# Schematic.net
KiCad netlist of a schematic drawn in Altium Designer
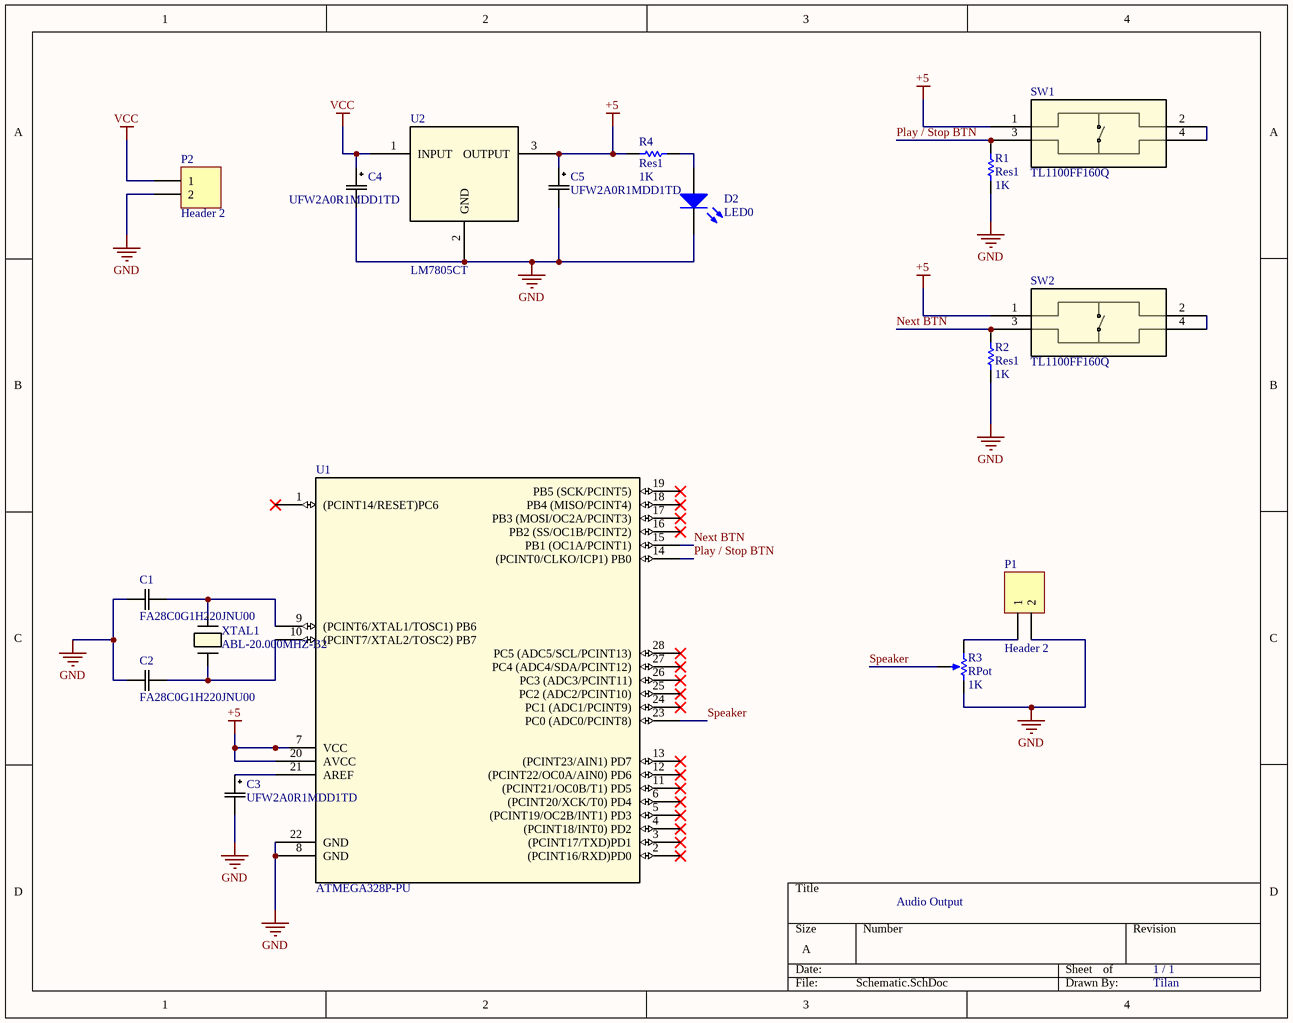
[diagram p0: Schematic.SchDoc]

(export (version "E")
  (design (tool "Eeschema 10.0.6"))
  (components
    (comp (ref "C1")
      (value "FA28C0G1H220JNU00")
      (footprint "CAP_FA28_TDK")
      (description "No Description Available")
      (fields (field (name "COPYRIGHT") "Copyright (C) 2018 Accelerated Designs. All rights reserved"))
      (libsource (lib "22pfcap") (part "FA28C0G1H220JNU00"))
    )
    (comp (ref "C2")
      (value "FA28C0G1H220JNU00")
      (footprint "CAP_FA28_TDK")
      (description "No Description Available")
      (fields (field (name "COPYRIGHT") "Copyright (C) 2018 Accelerated Designs. All rights reserved"))
      (libsource (lib "22pfcap") (part "FA28C0G1H220JNU00"))
    )
    (comp (ref "C3")
      (value "UFW2A0R1MDD1TD")
      (footprint "CAP_UEP_5X11_NCH")
      (description "No Description Available")
      (fields (field (name "COPYRIGHT") "Copyright (C) 2018 Accelerated Designs. All rights reserved"))
      (libsource (lib "Pollcap") (part "UFW2A0R1MDD1TD"))
    )
    (comp (ref "C4")
      (value "UFW2A0R1MDD1TD")
      (footprint "CAP_UEP_5X11_NCH")
      (description "No Description Available")
      (fields (field (name "COPYRIGHT") "Copyright (C) 2018 Accelerated Designs. All rights reserved"))
      (libsource (lib "Pollcap") (part "UFW2A0R1MDD1TD"))
    )
    (comp (ref "C5")
      (value "UFW2A0R1MDD1TD")
      (footprint "CAP_UEP_5X11_NCH")
      (description "No Description Available")
      (fields (field (name "COPYRIGHT") "Copyright (C) 2018 Accelerated Designs. All rights reserved"))
      (libsource (lib "Pollcap") (part "UFW2A0R1MDD1TD"))
    )
    (comp (ref "D2")
      (value "LED0")
      (footprint "LED-0")
      (description "Typical INFRARED GaAs LED")
      (fields (field (name "PUBLISHER") "Altium Limited"))
      (libsource (lib "Miscellaneous Devices") (part "LED0"))
    )
    (comp (ref "P1")
      (value "Header 2")
      (footprint "HDR1X2")
      (description "Header, 2-Pin")
      (fields (field (name "PUBLISHER") "Altium Limited"))
      (libsource (lib "Miscellaneous Connectors") (part "Header 2"))
    )
    (comp (ref "P2")
      (value "Header 2")
      (footprint "HDR1X2")
      (description "Header, 2-Pin")
      (fields (field (name "PUBLISHER") "Altium Limited"))
      (libsource (lib "") (part "Header 2_1"))
    )
    (comp (ref "R1")
      (value "Res1")
      (footprint "AXIAL-0.3")
      (description "Resistor")
      (fields (field (name "ALTIUM_VALUE") "1K") (field (name "PUBLISHER") "Altium Limited"))
      (libsource (lib "Miscellaneous Devices") (part "Res1"))
    )
    (comp (ref "R2")
      (value "Res1")
      (footprint "AXIAL-0.3")
      (description "Resistor")
      (fields (field (name "ALTIUM_VALUE") "1K") (field (name "PUBLISHER") "Altium Limited"))
      (libsource (lib "Miscellaneous Devices") (part "Res1"))
    )
    (comp (ref "R3")
      (value "RPot")
      (footprint "VR5")
      (description "Potentiometer")
      (fields (field (name "ALTIUM_VALUE") "1K") (field (name "PUBLISHER") "Altium Limited"))
      (libsource (lib "Miscellaneous Devices") (part "RPot"))
    )
    (comp (ref "R4")
      (value "Res1")
      (footprint "AXIAL-0.3")
      (description "Resistor")
      (fields (field (name "ALTIUM_VALUE") "1K") (field (name "PUBLISHER") "Altium Limited"))
      (libsource (lib "Miscellaneous Devices") (part "Res1"))
    )
    (comp (ref "SW1")
      (value "TL1100FF160Q")
      (footprint "TL1100F")
      (description "No Description Available")
      (fields (field (name "COPYRIGHT") "Copyright (C) 2018 Accelerated Designs. All rights reserved"))
      (libsource (lib "Tacktileswitch") (part "TL1100FF160Q"))
    )
    (comp (ref "SW2")
      (value "TL1100FF160Q")
      (footprint "TL1100F")
      (description "No Description Available")
      (fields (field (name "COPYRIGHT") "Copyright (C) 2018 Accelerated Designs. All rights reserved"))
      (libsource (lib "Tacktileswitch") (part "TL1100FF160Q"))
    )
    (comp (ref "U1")
      (value "ATMEGA328P-PU")
      (footprint "28P3_ATM")
      (description "No Description Available")
      (fields (field (name "COPYRIGHT") "Copyright (C) 2018 Accelerated Designs. All rights reserved"))
      (libsource (lib "ATMEGA328P-PU") (part "ATMEGA328P-PU"))
    )
    (comp (ref "U2")
      (value "LM7805CT")
      (footprint "TO-220_FAS")
      (description "No Description Available")
      (fields (field (name "COPYRIGHT") "Copyright (C) 2018 Accelerated Designs. All rights reserved"))
      (libsource (lib "LM7805new") (part "LM7805CT"))
    )
    (comp (ref "XTAL1")
      (value "ABL-20.000MHZ-B2")
      (footprint "XTAL_ABL_ABR")
      (description "No Description Available")
      (fields (field (name "COPYRIGHT") "Copyright (C) 2018 Accelerated Designs. All rights reserved"))
      (libsource (lib "xtal") (part "ABL-20.000MHZ-B2"))
    )
  )
  (nets
    (net (code "1") (name "+5") (class "Default")
      (node (ref "C5") (pin "1") (pinfunction "1_1") (pintype "passive"))
      (node (ref "R4") (pin "1") (pinfunction "1_1") (pintype "passive"))
      (node (ref "SW1") (pin "1") (pinfunction "1_1") (pintype "passive"))
      (node (ref "SW2") (pin "1") (pinfunction "1_1") (pintype "passive"))
      (node (ref "U1") (pin "20") (pinfunction "AVCC_20") (pintype "power_in"))
      (node (ref "U1") (pin "7") (pinfunction "VCC_7") (pintype "power_in"))
      (node (ref "U2") (pin "3") (pinfunction "OUTPUT_3") (pintype "power_in"))
    )
    (net (code "2") (name "/Next BTN") (class "Default")
      (node (ref "R2") (pin "1") (pinfunction "1_1") (pintype "passive"))
      (node (ref "SW2") (pin "3") (pinfunction "3_3") (pintype "passive"))
      (node (ref "U1") (pin "15") (pinfunction "PB1_(OC1A/PCINT1)_15") (pintype "bidirectional"))
    )
    (net (code "3") (name "/Play {slash} Stop BTN") (class "Default")
      (node (ref "R1") (pin "2") (pinfunction "2_2") (pintype "passive"))
      (node (ref "SW1") (pin "3") (pinfunction "3_3") (pintype "passive"))
      (node (ref "U1") (pin "14") (pinfunction "(PCINT0/CLKO/ICP1)_PB0_14") (pintype "bidirectional"))
    )
    (net (code "4") (name "/Speaker") (class "Default")
      (node (ref "R3") (pin "3") (pinfunction "TAP_3") (pintype "passive"))
      (node (ref "U1") (pin "23") (pinfunction "PC0_(ADC0/PCINT8)_23") (pintype "bidirectional"))
    )
    (net (code "5") (name "GND") (class "Default")
      (node (ref "C1") (pin "1") (pinfunction "1_1") (pintype "passive"))
      (node (ref "C2") (pin "1") (pinfunction "1_1") (pintype "passive"))
      (node (ref "C3") (pin "2") (pinfunction "2_2") (pintype "passive"))
      (node (ref "C4") (pin "2") (pinfunction "2_2") (pintype "passive"))
      (node (ref "C5") (pin "2") (pinfunction "2_2") (pintype "passive"))
      (node (ref "D2") (pin "2") (pinfunction "K_2") (pintype "passive"))
      (node (ref "P1") (pin "2") (pinfunction "2_2") (pintype "passive"))
      (node (ref "P2") (pin "2") (pinfunction "2_2") (pintype "passive"))
      (node (ref "R1") (pin "1") (pinfunction "1_1") (pintype "passive"))
      (node (ref "R2") (pin "2") (pinfunction "2_2") (pintype "passive"))
      (node (ref "R3") (pin "2") (pinfunction "BOT_2") (pintype "passive"))
      (node (ref "U1") (pin "22") (pinfunction "GND_22") (pintype "power_in"))
      (node (ref "U1") (pin "8") (pinfunction "GND_8") (pintype "power_in"))
      (node (ref "U2") (pin "2") (pinfunction "GND_2") (pintype "power_in"))
    )
    (net (code "6") (name "Net-(D2-A)") (class "Default")
      (node (ref "D2") (pin "1") (pinfunction "A_1") (pintype "passive"))
      (node (ref "R4") (pin "2") (pinfunction "2_2") (pintype "passive"))
    )
    (net (code "7") (name "Net-(R3-TOP)") (class "Default")
      (node (ref "P1") (pin "1") (pinfunction "1_1") (pintype "passive"))
      (node (ref "R3") (pin "1") (pinfunction "TOP_1") (pintype "passive"))
    )
    (net (code "8") (name "Net-(SW1-Pad2)") (class "Default")
      (node (ref "SW1") (pin "2") (pinfunction "2_2") (pintype "passive"))
      (node (ref "SW1") (pin "4") (pinfunction "4_4") (pintype "passive"))
    )
    (net (code "9") (name "Net-(SW2-Pad2)") (class "Default")
      (node (ref "SW2") (pin "2") (pinfunction "2_2") (pintype "passive"))
      (node (ref "SW2") (pin "4") (pinfunction "4_4") (pintype "passive"))
    )
    (net (code "10") (name "Net-(U1-(PCINT6{slash}XTAL1{slash}TOSC1)_PB6)") (class "Default")
      (node (ref "C1") (pin "2") (pinfunction "2_2") (pintype "passive"))
      (node (ref "U1") (pin "9") (pinfunction "(PCINT6/XTAL1/TOSC1)_PB6_9") (pintype "bidirectional"))
      (node (ref "XTAL1") (pin "2") (pinfunction "2_2") (pintype "passive"))
    )
    (net (code "11") (name "Net-(U1-(PCINT7{slash}XTAL2{slash}TOSC2)_PB7)") (class "Default")
      (node (ref "C2") (pin "2") (pinfunction "2_2") (pintype "passive"))
      (node (ref "U1") (pin "10") (pinfunction "(PCINT7/XTAL2/TOSC2)_PB7_10") (pintype "bidirectional"))
      (node (ref "XTAL1") (pin "1") (pinfunction "1_1") (pintype "passive"))
    )
    (net (code "12") (name "Net-(U1-AREF)") (class "Default")
      (node (ref "C3") (pin "1") (pinfunction "1_1") (pintype "passive"))
      (node (ref "U1") (pin "21") (pinfunction "AREF_21") (pintype "passive"))
    )
    (net (code "13") (name "VCC") (class "Default")
      (node (ref "C4") (pin "1") (pinfunction "1_1") (pintype "passive"))
      (node (ref "P2") (pin "1") (pinfunction "1_1") (pintype "passive"))
      (node (ref "U2") (pin "1") (pinfunction "INPUT_1") (pintype "power_in"))
    )
    (net (code "14") (name "unconnected-(U1-(PCINT14{slash}RESET)PC6-Pad1)") (class "Default")
      (node (ref "U1") (pin "1") (pinfunction "(PCINT14/RESET)PC6_1") (pintype "bidirectional+no_connect"))
    )
    (net (code "15") (name "unconnected-(U1-(PCINT16{slash}RXD)PD0-Pad2)") (class "Default")
      (node (ref "U1") (pin "2") (pinfunction "(PCINT16/RXD)PD0_2") (pintype "bidirectional+no_connect"))
    )
    (net (code "16") (name "unconnected-(U1-(PCINT17{slash}TXD)PD1-Pad3)") (class "Default")
      (node (ref "U1") (pin "3") (pinfunction "(PCINT17/TXD)PD1_3") (pintype "bidirectional+no_connect"))
    )
    (net (code "17") (name "unconnected-(U1-(PCINT18{slash}INT0)_PD2-Pad4)") (class "Default")
      (node (ref "U1") (pin "4") (pinfunction "(PCINT18/INT0)_PD2_4") (pintype "bidirectional+no_connect"))
    )
    (net (code "18") (name "unconnected-(U1-(PCINT19{slash}OC2B{slash}INT1)_PD3-Pad5)") (class "Default")
      (node (ref "U1") (pin "5") (pinfunction "(PCINT19/OC2B/INT1)_PD3_5") (pintype "bidirectional+no_connect"))
    )
    (net (code "19") (name "unconnected-(U1-(PCINT20{slash}XCK{slash}T0)_PD4-Pad6)") (class "Default")
      (node (ref "U1") (pin "6") (pinfunction "(PCINT20/XCK/T0)_PD4_6") (pintype "bidirectional+no_connect"))
    )
    (net (code "20") (name "unconnected-(U1-(PCINT21{slash}OC0B{slash}T1)_PD5-Pad11)") (class "Default")
      (node (ref "U1") (pin "11") (pinfunction "(PCINT21/OC0B/T1)_PD5_11") (pintype "bidirectional+no_connect"))
    )
    (net (code "21") (name "unconnected-(U1-(PCINT22{slash}OC0A{slash}AIN0)_PD6-Pad12)") (class "Default")
      (node (ref "U1") (pin "12") (pinfunction "(PCINT22/OC0A/AIN0)_PD6_12") (pintype "bidirectional+no_connect"))
    )
    (net (code "22") (name "unconnected-(U1-(PCINT23{slash}AIN1)_PD7-Pad13)") (class "Default")
      (node (ref "U1") (pin "13") (pinfunction "(PCINT23/AIN1)_PD7_13") (pintype "bidirectional+no_connect"))
    )
    (net (code "23") (name "unconnected-(U1-PB2_(SS{slash}OC1B{slash}PCINT2)-Pad16)") (class "Default")
      (node (ref "U1") (pin "16") (pinfunction "PB2_(SS/OC1B/PCINT2)_16") (pintype "bidirectional+no_connect"))
    )
    (net (code "24") (name "unconnected-(U1-PB3_(MOSI{slash}OC2A{slash}PCINT3)-Pad17)") (class "Default")
      (node (ref "U1") (pin "17") (pinfunction "PB3_(MOSI/OC2A/PCINT3)_17") (pintype "bidirectional+no_connect"))
    )
    (net (code "25") (name "unconnected-(U1-PB4_(MISO{slash}PCINT4)-Pad18)") (class "Default")
      (node (ref "U1") (pin "18") (pinfunction "PB4_(MISO/PCINT4)_18") (pintype "bidirectional+no_connect"))
    )
    (net (code "26") (name "unconnected-(U1-PB5_(SCK{slash}PCINT5)-Pad19)") (class "Default")
      (node (ref "U1") (pin "19") (pinfunction "PB5_(SCK/PCINT5)_19") (pintype "bidirectional+no_connect"))
    )
    (net (code "27") (name "unconnected-(U1-PC1_(ADC1{slash}PCINT9)-Pad24)") (class "Default")
      (node (ref "U1") (pin "24") (pinfunction "PC1_(ADC1/PCINT9)_24") (pintype "bidirectional+no_connect"))
    )
    (net (code "28") (name "unconnected-(U1-PC2_(ADC2{slash}PCINT10)-Pad25)") (class "Default")
      (node (ref "U1") (pin "25") (pinfunction "PC2_(ADC2/PCINT10)_25") (pintype "bidirectional+no_connect"))
    )
    (net (code "29") (name "unconnected-(U1-PC3_(ADC3{slash}PCINT11)-Pad26)") (class "Default")
      (node (ref "U1") (pin "26") (pinfunction "PC3_(ADC3/PCINT11)_26") (pintype "bidirectional+no_connect"))
    )
    (net (code "30") (name "unconnected-(U1-PC4_(ADC4{slash}SDA{slash}PCINT12)-Pad27)") (class "Default")
      (node (ref "U1") (pin "27") (pinfunction "PC4_(ADC4/SDA/PCINT12)_27") (pintype "bidirectional+no_connect"))
    )
    (net (code "31") (name "unconnected-(U1-PC5_(ADC5{slash}SCL{slash}PCINT13)-Pad28)") (class "Default")
      (node (ref "U1") (pin "28") (pinfunction "PC5_(ADC5/SCL/PCINT13)_28") (pintype "bidirectional+no_connect"))
    )
  )
)
